# DWM1000Breakout.net
KiCad netlist of a schematic drawn in Altium Designer
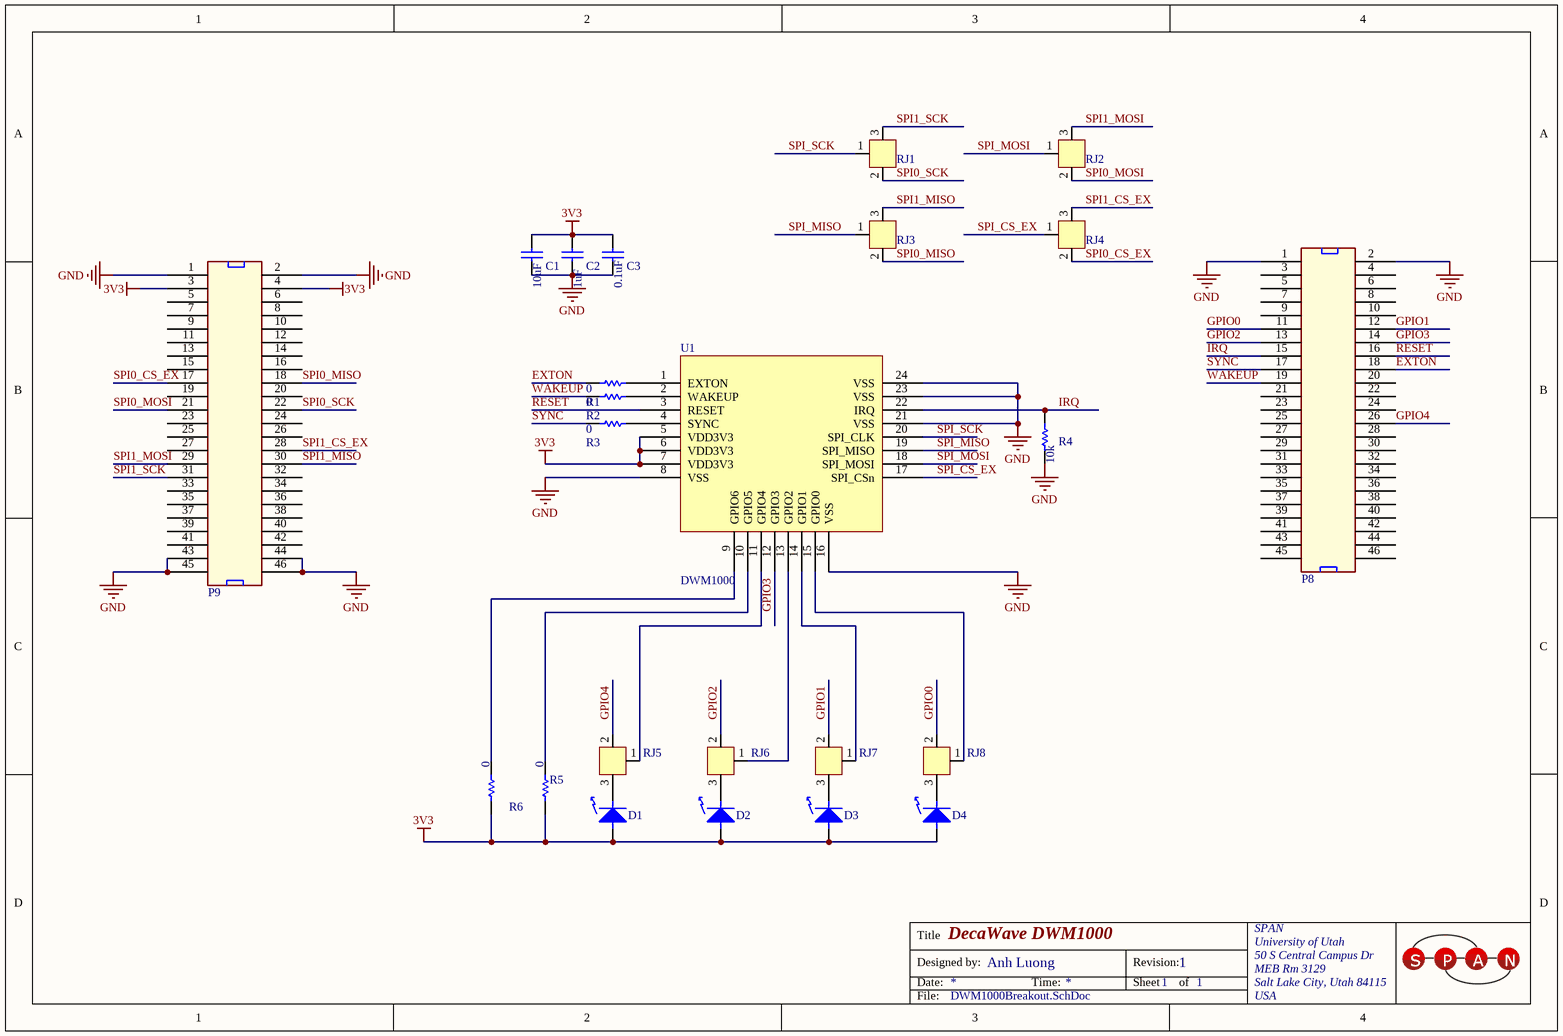
[diagram p0: DWM1000Breakout.SchDoc]

(export (version "E")
  (design (tool "Eeschema 10.0.6"))
  (components
    (comp (ref "C1")
      (value "GRM188R60J106ME47D")
      (footprint "CAPC1608X08N (0603)")
      (description "CAP CER 10UF 6.3V 20% X5R 0603")
      (fields
        (field (name "MANUFACTURER") "Murata Electronics North America")
        (field (name "TOLERANCE") "±20%")
      )
      (libsource (lib "DWM1000Breakout") (part "GRM188R60J106ME47D"))
    )
    (comp (ref "C2")
      (value "GRM188R61A105KA61D")
      (footprint "CAPC1608X08N (0603)")
      (description "CAP CER 1UF 10V 10% X5R 0603")
      (fields
        (field (name "MANUFACTURER") "Murata Electronics North America")
        (field (name "TOLERANCE") "±10%")
      )
      (libsource (lib "DWM1000Breakout") (part "GRM188R61A105KA61D"))
    )
    (comp (ref "C3")
      (value "GRM188R71C104KA01D")
      (footprint "CAPC1608X08N (0603)")
      (description "CAP CER 0.1UF 16V 10% X7R 0603")
      (fields
        (field (name "MANUFACTURER") "Murata Electronics North America")
        (field (name "TOLERANCE") "±10%")
      )
      (libsource (lib "DWM1000Breakout") (part "GRM188R71C104KA01D"))
    )
    (comp (ref "D1")
      (value "LG Q971-KN-1")
      (footprint "CHIPLED0603")
      (description "LED CHIPLED 570NM GREEN 0603 SMD")
      (fields (field (name "MANUFACTURER") "OSRAM Opto Semiconductors Inc"))
      (libsource (lib "DWM1000Breakout") (part "LG Q971-KN-1"))
    )
    (comp (ref "D2")
      (value "LG Q971-KN-1")
      (footprint "CHIPLED0603")
      (description "LED CHIPLED 570NM GREEN 0603 SMD")
      (fields (field (name "MANUFACTURER") "OSRAM Opto Semiconductors Inc"))
      (libsource (lib "DWM1000Breakout") (part "LG Q971-KN-1"))
    )
    (comp (ref "D3")
      (value "LG Q971-KN-1")
      (footprint "CHIPLED0603")
      (description "LED CHIPLED 570NM GREEN 0603 SMD")
      (fields (field (name "MANUFACTURER") "OSRAM Opto Semiconductors Inc"))
      (libsource (lib "DWM1000Breakout") (part "LG Q971-KN-1"))
    )
    (comp (ref "D4")
      (value "LG Q971-KN-1")
      (footprint "CHIPLED0603")
      (description "LED CHIPLED 570NM GREEN 0603 SMD")
      (fields (field (name "MANUFACTURER") "OSRAM Opto Semiconductors Inc"))
      (libsource (lib "DWM1000Breakout") (part "LG Q971-KN-1"))
    )
    (comp (ref "P8")
      (value "PREC023DAAN-RC")
      (footprint "HEADER23X2")
      (description "CONN HEADER .100\" DUAL STR 46POS")
      (fields (field (name "MANUFACTURER") "Sullins Connector Solutions"))
      (libsource (lib "Chronos") (part "PREC023DAAN-RC"))
    )
    (comp (ref "P9")
      (value "PREC023DAAN-RC")
      (footprint "HEADER23X2")
      (description "CONN HEADER .100\" DUAL STR 46POS")
      (fields (field (name "MANUFACTURER") "Sullins Connector Solutions"))
      (libsource (lib "Chronos") (part "PREC023DAAN-RC"))
    )
    (comp (ref "R1")
      (value "MCR03ERTJ000")
      (footprint "RESC1608X06N (0603)")
      (description "RES 0.0 OHM 1/10W JUMP 0603 SMD")
      (fields (field (name "MANUFACTURER") "Rohm Semiconductor") (field (name "TOLERANCE") "Jumper"))
      (libsource (lib "DWM1000Breakout") (part "MCR03ERTJ000"))
    )
    (comp (ref "R2")
      (value "MCR03ERTJ000")
      (footprint "RESC1608X06N (0603)")
      (description "RES 0.0 OHM 1/10W JUMP 0603 SMD")
      (fields (field (name "MANUFACTURER") "Rohm Semiconductor") (field (name "TOLERANCE") "Jumper"))
      (libsource (lib "DWM1000Breakout") (part "MCR03ERTJ000"))
    )
    (comp (ref "R3")
      (value "MCR03ERTJ000")
      (footprint "RESC1608X06N (0603)")
      (description "RES 0.0 OHM 1/10W JUMP 0603 SMD")
      (fields (field (name "MANUFACTURER") "Rohm Semiconductor") (field (name "TOLERANCE") "Jumper"))
      (libsource (lib "DWM1000Breakout") (part "MCR03ERTJ000"))
    )
    (comp (ref "R4")
      (value "MCR03ERTJ103")
      (footprint "RESC1608X06N (0603)")
      (description "RES 10K OHM 1/10W 5% 0603 SMD")
      (fields (field (name "MANUFACTURER") "Rohm Semiconductor") (field (name "TOLERANCE") "±5%"))
      (libsource (lib "DWM1000Breakout") (part "MCR03ERTJ103"))
    )
    (comp (ref "R5")
      (value "MCR03ERTJ000")
      (footprint "RESC1608X06N (0603)")
      (description "RES 0.0 OHM 1/10W JUMP 0603 SMD")
      (fields (field (name "MANUFACTURER") "Rohm Semiconductor") (field (name "TOLERANCE") "Jumper"))
      (libsource (lib "DWM1000Breakout") (part "MCR03ERTJ000"))
    )
    (comp (ref "R6")
      (value "MCR03ERTJ000")
      (footprint "RESC1608X06N (0603)")
      (description "RES 0.0 OHM 1/10W JUMP 0603 SMD")
      (fields (field (name "MANUFACTURER") "Rohm Semiconductor") (field (name "TOLERANCE") "Jumper"))
      (libsource (lib "DWM1000Breakout") (part "MCR03ERTJ000"))
    )
    (comp (ref "RJ1")
      (value "R_J")
      (footprint "RJ")
      (description "Resistor Jumper")
      (libsource (lib "DWM1000Breakout") (part "R_J"))
    )
    (comp (ref "RJ2")
      (value "R_J")
      (footprint "RJ")
      (description "Resistor Jumper")
      (libsource (lib "DWM1000Breakout") (part "R_J"))
    )
    (comp (ref "RJ3")
      (value "R_J")
      (footprint "RJ")
      (description "Resistor Jumper")
      (libsource (lib "DWM1000Breakout") (part "R_J"))
    )
    (comp (ref "RJ4")
      (value "R_J")
      (footprint "RJ")
      (description "Resistor Jumper")
      (libsource (lib "DWM1000Breakout") (part "R_J"))
    )
    (comp (ref "RJ5")
      (value "R_J")
      (footprint "RJ")
      (description "Resistor Jumper")
      (libsource (lib "") (part "R_J_1"))
    )
    (comp (ref "RJ6")
      (value "R_J")
      (footprint "RJ")
      (description "Resistor Jumper")
      (libsource (lib "") (part "R_J_1"))
    )
    (comp (ref "RJ7")
      (value "R_J")
      (footprint "RJ")
      (description "Resistor Jumper")
      (libsource (lib "") (part "R_J_1"))
    )
    (comp (ref "RJ8")
      (value "R_J")
      (footprint "RJ")
      (description "Resistor Jumper")
      (libsource (lib "") (part "R_J_1"))
    )
    (comp (ref "U1")
      (value "DWM1000")
      (footprint "DWM1000")
      (description "MOD IEEE802.15.4-2011 UWB TXRX")
      (fields (field (name "MANUFACTURER") "Decawave Limited"))
      (libsource (lib "DWM1000Breakout") (part "DWM1000"))
    )
  )
  (nets
    (net (code "1") (name "/EXTON") (class "Default")
      (node (ref "P8") (pin "18") (pinfunction "34_18") (pintype "passive"))
      (node (ref "R1") (pin "1") (pinfunction "1_1") (pintype "passive"))
    )
    (net (code "2") (name "/GPIO0") (class "Default")
      (node (ref "P8") (pin "11") (pinfunction "6_11") (pintype "passive"))
      (node (ref "RJ8") (pin "2") (pinfunction "2_2") (pintype "passive"))
    )
    (net (code "3") (name "/GPIO1") (class "Default")
      (node (ref "P8") (pin "12") (pinfunction "31_12") (pintype "passive"))
      (node (ref "RJ7") (pin "2") (pinfunction "2_2") (pintype "passive"))
    )
    (net (code "4") (name "/GPIO2") (class "Default")
      (node (ref "P8") (pin "13") (pinfunction "7_13") (pintype "passive"))
      (node (ref "RJ6") (pin "2") (pinfunction "2_2") (pintype "passive"))
    )
    (net (code "5") (name "/GPIO3") (class "Default")
      (node (ref "P8") (pin "14") (pinfunction "32_14") (pintype "passive"))
      (node (ref "U1") (pin "12") (pinfunction "GPIO3_12") (pintype "passive"))
    )
    (net (code "6") (name "/GPIO4") (class "Default")
      (node (ref "P8") (pin "26") (pinfunction "38_26") (pintype "passive"))
      (node (ref "RJ5") (pin "2") (pinfunction "2_2") (pintype "passive"))
    )
    (net (code "7") (name "/IRQ") (class "Default")
      (node (ref "P8") (pin "15") (pinfunction "8_15") (pintype "passive"))
      (node (ref "R4") (pin "2") (pinfunction "2_2") (pintype "passive"))
      (node (ref "U1") (pin "22") (pinfunction "IRQ_22") (pintype "passive"))
    )
    (net (code "8") (name "/RESET") (class "Default")
      (node (ref "P8") (pin "16") (pinfunction "33_16") (pintype "passive"))
      (node (ref "U1") (pin "3") (pinfunction "RESET_3") (pintype "passive"))
    )
    (net (code "9") (name "/SPI0_CS_EX") (class "Default")
      (node (ref "P9") (pin "17") (pinfunction "9_17") (pintype "passive"))
      (node (ref "RJ4") (pin "2") (pinfunction "2_2") (pintype "passive"))
    )
    (net (code "10") (name "/SPI0_MISO") (class "Default")
      (node (ref "P9") (pin "18") (pinfunction "34_18") (pintype "passive"))
      (node (ref "RJ3") (pin "2") (pinfunction "2_2") (pintype "passive"))
    )
    (net (code "11") (name "/SPI0_MOSI") (class "Default")
      (node (ref "P9") (pin "21") (pinfunction "11_21") (pintype "passive"))
      (node (ref "RJ2") (pin "2") (pinfunction "2_2") (pintype "passive"))
    )
    (net (code "12") (name "/SPI0_SCK") (class "Default")
      (node (ref "P9") (pin "22") (pinfunction "36_22") (pintype "passive"))
      (node (ref "RJ1") (pin "2") (pinfunction "2_2") (pintype "passive"))
    )
    (net (code "13") (name "/SPI1_CS_EX") (class "Default")
      (node (ref "P9") (pin "28") (pinfunction "39_28") (pintype "passive"))
      (node (ref "RJ4") (pin "3") (pinfunction "3_3") (pintype "passive"))
    )
    (net (code "14") (name "/SPI1_MISO") (class "Default")
      (node (ref "P9") (pin "30") (pinfunction "40_30") (pintype "passive"))
      (node (ref "RJ3") (pin "3") (pinfunction "3_3") (pintype "passive"))
    )
    (net (code "15") (name "/SPI1_MOSI") (class "Default")
      (node (ref "P9") (pin "29") (pinfunction "15_29") (pintype "passive"))
      (node (ref "RJ2") (pin "3") (pinfunction "3_3") (pintype "passive"))
    )
    (net (code "16") (name "/SPI1_SCK") (class "Default")
      (node (ref "P9") (pin "31") (pinfunction "16_31") (pintype "passive"))
      (node (ref "RJ1") (pin "3") (pinfunction "3_3") (pintype "passive"))
    )
    (net (code "17") (name "/SPI_CS_EX") (class "Default")
      (node (ref "RJ4") (pin "1") (pinfunction "1_1") (pintype "passive"))
      (node (ref "U1") (pin "17") (pinfunction "SPI_CSn_17") (pintype "passive"))
    )
    (net (code "18") (name "/SPI_MISO") (class "Default")
      (node (ref "RJ3") (pin "1") (pinfunction "1_1") (pintype "passive"))
      (node (ref "U1") (pin "19") (pinfunction "SPI_MISO_19") (pintype "passive"))
    )
    (net (code "19") (name "/SPI_MOSI") (class "Default")
      (node (ref "RJ2") (pin "1") (pinfunction "1_1") (pintype "passive"))
      (node (ref "U1") (pin "18") (pinfunction "SPI_MOSI_18") (pintype "passive"))
    )
    (net (code "20") (name "/SPI_SCK") (class "Default")
      (node (ref "RJ1") (pin "1") (pinfunction "1_1") (pintype "passive"))
      (node (ref "U1") (pin "20") (pinfunction "SPI_CLK_20") (pintype "passive"))
    )
    (net (code "21") (name "/SYNC") (class "Default")
      (node (ref "P8") (pin "17") (pinfunction "9_17") (pintype "passive"))
      (node (ref "R3") (pin "1") (pinfunction "1_1") (pintype "passive"))
    )
    (net (code "22") (name "/WAKEUP") (class "Default")
      (node (ref "P8") (pin "19") (pinfunction "10_19") (pintype "passive"))
      (node (ref "R2") (pin "1") (pinfunction "1_1") (pintype "passive"))
    )
    (net (code "23") (name "3V3") (class "Default")
      (node (ref "C1") (pin "2") (pinfunction "2_2") (pintype "passive"))
      (node (ref "C2") (pin "2") (pinfunction "2_2") (pintype "passive"))
      (node (ref "C3") (pin "2") (pinfunction "2_2") (pintype "passive"))
      (node (ref "D1") (pin "1") (pinfunction "1_1") (pintype "passive"))
      (node (ref "D2") (pin "1") (pinfunction "1_1") (pintype "passive"))
      (node (ref "D3") (pin "1") (pinfunction "1_1") (pintype "passive"))
      (node (ref "D4") (pin "1") (pinfunction "1_1") (pintype "passive"))
      (node (ref "P9") (pin "3") (pinfunction "2_3") (pintype "passive"))
      (node (ref "P9") (pin "4") (pinfunction "27_4") (pintype "passive"))
      (node (ref "R5") (pin "2") (pinfunction "2_2") (pintype "passive"))
      (node (ref "R6") (pin "2") (pinfunction "2_2") (pintype "passive"))
      (node (ref "U1") (pin "5") (pinfunction "VDD3V3_5") (pintype "passive"))
      (node (ref "U1") (pin "6") (pinfunction "VDD3V3_6") (pintype "passive"))
      (node (ref "U1") (pin "7") (pinfunction "VDD3V3_7") (pintype "passive"))
    )
    (net (code "24") (name "GND") (class "Default")
      (node (ref "C1") (pin "1") (pinfunction "1_1") (pintype "passive"))
      (node (ref "C2") (pin "1") (pinfunction "1_1") (pintype "passive"))
      (node (ref "C3") (pin "1") (pinfunction "1_1") (pintype "passive"))
      (node (ref "P8") (pin "1") (pinfunction "1_1") (pintype "passive"))
      (node (ref "P8") (pin "2") (pinfunction "26_2") (pintype "passive"))
      (node (ref "P9") (pin "1") (pinfunction "1_1") (pintype "passive"))
      (node (ref "P9") (pin "2") (pinfunction "26_2") (pintype "passive"))
      (node (ref "P9") (pin "43") (pinfunction "22_43") (pintype "passive"))
      (node (ref "P9") (pin "44") (pinfunction "47_44") (pintype "passive"))
      (node (ref "P9") (pin "45") (pinfunction "23_45") (pintype "passive"))
      (node (ref "P9") (pin "46") (pinfunction "48_46") (pintype "passive"))
      (node (ref "R4") (pin "1") (pinfunction "1_1") (pintype "passive"))
      (node (ref "U1") (pin "16") (pinfunction "VSS_16") (pintype "passive"))
      (node (ref "U1") (pin "21") (pinfunction "VSS_21") (pintype "passive"))
      (node (ref "U1") (pin "23") (pinfunction "VSS_23") (pintype "passive"))
      (node (ref "U1") (pin "24") (pinfunction "VSS_24") (pintype "passive"))
      (node (ref "U1") (pin "8") (pinfunction "VSS_8") (pintype "passive"))
    )
    (net (code "25") (name "Net-(D1-Pad2)") (class "Default")
      (node (ref "D1") (pin "2") (pinfunction "2_2") (pintype "passive"))
      (node (ref "RJ5") (pin "3") (pinfunction "3_3") (pintype "passive"))
    )
    (net (code "26") (name "Net-(D2-Pad2)") (class "Default")
      (node (ref "D2") (pin "2") (pinfunction "2_2") (pintype "passive"))
      (node (ref "RJ6") (pin "3") (pinfunction "3_3") (pintype "passive"))
    )
    (net (code "27") (name "Net-(D3-Pad2)") (class "Default")
      (node (ref "D3") (pin "2") (pinfunction "2_2") (pintype "passive"))
      (node (ref "RJ7") (pin "3") (pinfunction "3_3") (pintype "passive"))
    )
    (net (code "28") (name "Net-(D4-Pad2)") (class "Default")
      (node (ref "D4") (pin "2") (pinfunction "2_2") (pintype "passive"))
      (node (ref "RJ8") (pin "3") (pinfunction "3_3") (pintype "passive"))
    )
    (net (code "29") (name "Net-(U1-EXTON)") (class "Default")
      (node (ref "R1") (pin "2") (pinfunction "2_2") (pintype "passive"))
      (node (ref "U1") (pin "1") (pinfunction "EXTON_1") (pintype "passive"))
    )
    (net (code "30") (name "Net-(U1-GPIO0)") (class "Default")
      (node (ref "RJ8") (pin "1") (pinfunction "1_1") (pintype "passive"))
      (node (ref "U1") (pin "15") (pinfunction "GPIO0_15") (pintype "passive"))
    )
    (net (code "31") (name "Net-(U1-GPIO1)") (class "Default")
      (node (ref "RJ7") (pin "1") (pinfunction "1_1") (pintype "passive"))
      (node (ref "U1") (pin "14") (pinfunction "GPIO1_14") (pintype "passive"))
    )
    (net (code "32") (name "Net-(U1-GPIO2)") (class "Default")
      (node (ref "RJ6") (pin "1") (pinfunction "1_1") (pintype "passive"))
      (node (ref "U1") (pin "13") (pinfunction "GPIO2_13") (pintype "passive"))
    )
    (net (code "33") (name "Net-(U1-GPIO4)") (class "Default")
      (node (ref "RJ5") (pin "1") (pinfunction "1_1") (pintype "passive"))
      (node (ref "U1") (pin "11") (pinfunction "GPIO4_11") (pintype "passive"))
    )
    (net (code "34") (name "Net-(U1-GPIO5)") (class "Default")
      (node (ref "R5") (pin "1") (pinfunction "1_1") (pintype "passive"))
      (node (ref "U1") (pin "10") (pinfunction "GPIO5_10") (pintype "passive"))
    )
    (net (code "35") (name "Net-(U1-GPIO6)") (class "Default")
      (node (ref "R6") (pin "1") (pinfunction "1_1") (pintype "passive"))
      (node (ref "U1") (pin "9") (pinfunction "GPIO6_9") (pintype "passive"))
    )
    (net (code "36") (name "Net-(U1-SYNC)") (class "Default")
      (node (ref "R3") (pin "2") (pinfunction "2_2") (pintype "passive"))
      (node (ref "U1") (pin "4") (pinfunction "SYNC_4") (pintype "passive"))
    )
    (net (code "37") (name "Net-(U1-WAKEUP)") (class "Default")
      (node (ref "R2") (pin "2") (pinfunction "2_2") (pintype "passive"))
      (node (ref "U1") (pin "2") (pinfunction "WAKEUP_2") (pintype "passive"))
    )
    (net (code "38") (name "unconnected-(P8-2-Pad3)") (class "Default")
      (node (ref "P8") (pin "3") (pinfunction "2_3") (pintype "passive"))
    )
    (net (code "39") (name "unconnected-(P8-3-Pad5)") (class "Default")
      (node (ref "P8") (pin "5") (pinfunction "3_5") (pintype "passive"))
    )
    (net (code "40") (name "unconnected-(P8-4-Pad7)") (class "Default")
      (node (ref "P8") (pin "7") (pinfunction "4_7") (pintype "passive"))
    )
    (net (code "41") (name "unconnected-(P8-5-Pad9)") (class "Default")
      (node (ref "P8") (pin "9") (pinfunction "5_9") (pintype "passive"))
    )
    (net (code "42") (name "unconnected-(P8-11-Pad21)") (class "Default")
      (node (ref "P8") (pin "21") (pinfunction "11_21") (pintype "passive"))
    )
    (net (code "43") (name "unconnected-(P8-12-Pad23)") (class "Default")
      (node (ref "P8") (pin "23") (pinfunction "12_23") (pintype "passive"))
    )
    (net (code "44") (name "unconnected-(P8-13-Pad25)") (class "Default")
      (node (ref "P8") (pin "25") (pinfunction "13_25") (pintype "passive"))
    )
    (net (code "45") (name "unconnected-(P8-14-Pad27)") (class "Default")
      (node (ref "P8") (pin "27") (pinfunction "14_27") (pintype "passive"))
    )
    (net (code "46") (name "unconnected-(P8-15-Pad29)") (class "Default")
      (node (ref "P8") (pin "29") (pinfunction "15_29") (pintype "passive"))
    )
    (net (code "47") (name "unconnected-(P8-16-Pad31)") (class "Default")
      (node (ref "P8") (pin "31") (pinfunction "16_31") (pintype "passive"))
    )
    (net (code "48") (name "unconnected-(P8-17-Pad33)") (class "Default")
      (node (ref "P8") (pin "33") (pinfunction "17_33") (pintype "passive"))
    )
    (net (code "49") (name "unconnected-(P8-18-Pad35)") (class "Default")
      (node (ref "P8") (pin "35") (pinfunction "18_35") (pintype "passive"))
    )
    (net (code "50") (name "unconnected-(P8-19-Pad37)") (class "Default")
      (node (ref "P8") (pin "37") (pinfunction "19_37") (pintype "passive"))
    )
    (net (code "51") (name "unconnected-(P8-20-Pad39)") (class "Default")
      (node (ref "P8") (pin "39") (pinfunction "20_39") (pintype "passive"))
    )
    (net (code "52") (name "unconnected-(P8-21-Pad41)") (class "Default")
      (node (ref "P8") (pin "41") (pinfunction "21_41") (pintype "passive"))
    )
    (net (code "53") (name "unconnected-(P8-22-Pad43)") (class "Default")
      (node (ref "P8") (pin "43") (pinfunction "22_43") (pintype "passive"))
    )
    (net (code "54") (name "unconnected-(P8-23-Pad45)") (class "Default")
      (node (ref "P8") (pin "45") (pinfunction "23_45") (pintype "passive"))
    )
    (net (code "55") (name "unconnected-(P8-27-Pad4)") (class "Default")
      (node (ref "P8") (pin "4") (pinfunction "27_4") (pintype "passive"))
    )
    (net (code "56") (name "unconnected-(P8-28-Pad6)") (class "Default")
      (node (ref "P8") (pin "6") (pinfunction "28_6") (pintype "passive"))
    )
    (net (code "57") (name "unconnected-(P8-29-Pad8)") (class "Default")
      (node (ref "P8") (pin "8") (pinfunction "29_8") (pintype "passive"))
    )
    (net (code "58") (name "unconnected-(P8-30-Pad10)") (class "Default")
      (node (ref "P8") (pin "10") (pinfunction "30_10") (pintype "passive"))
    )
    (net (code "59") (name "unconnected-(P8-35-Pad20)") (class "Default")
      (node (ref "P8") (pin "20") (pinfunction "35_20") (pintype "passive"))
    )
    (net (code "60") (name "unconnected-(P8-36-Pad22)") (class "Default")
      (node (ref "P8") (pin "22") (pinfunction "36_22") (pintype "passive"))
    )
    (net (code "61") (name "unconnected-(P8-37-Pad24)") (class "Default")
      (node (ref "P8") (pin "24") (pinfunction "37_24") (pintype "passive"))
    )
    (net (code "62") (name "unconnected-(P8-39-Pad28)") (class "Default")
      (node (ref "P8") (pin "28") (pinfunction "39_28") (pintype "passive"))
    )
    (net (code "63") (name "unconnected-(P8-40-Pad30)") (class "Default")
      (node (ref "P8") (pin "30") (pinfunction "40_30") (pintype "passive"))
    )
    (net (code "64") (name "unconnected-(P8-41-Pad32)") (class "Default")
      (node (ref "P8") (pin "32") (pinfunction "41_32") (pintype "passive"))
    )
    (net (code "65") (name "unconnected-(P8-42-Pad34)") (class "Default")
      (node (ref "P8") (pin "34") (pinfunction "42_34") (pintype "passive"))
    )
    (net (code "66") (name "unconnected-(P8-43-Pad36)") (class "Default")
      (node (ref "P8") (pin "36") (pinfunction "43_36") (pintype "passive"))
    )
    (net (code "67") (name "unconnected-(P8-44-Pad38)") (class "Default")
      (node (ref "P8") (pin "38") (pinfunction "44_38") (pintype "passive"))
    )
    (net (code "68") (name "unconnected-(P8-45-Pad40)") (class "Default")
      (node (ref "P8") (pin "40") (pinfunction "45_40") (pintype "passive"))
    )
    (net (code "69") (name "unconnected-(P8-46-Pad42)") (class "Default")
      (node (ref "P8") (pin "42") (pinfunction "46_42") (pintype "passive"))
    )
    (net (code "70") (name "unconnected-(P8-47-Pad44)") (class "Default")
      (node (ref "P8") (pin "44") (pinfunction "47_44") (pintype "passive"))
    )
    (net (code "71") (name "unconnected-(P8-48-Pad46)") (class "Default")
      (node (ref "P8") (pin "46") (pinfunction "48_46") (pintype "passive"))
    )
    (net (code "72") (name "unconnected-(P9-3-Pad5)") (class "Default")
      (node (ref "P9") (pin "5") (pinfunction "3_5") (pintype "passive"))
    )
    (net (code "73") (name "unconnected-(P9-4-Pad7)") (class "Default")
      (node (ref "P9") (pin "7") (pinfunction "4_7") (pintype "passive"))
    )
    (net (code "74") (name "unconnected-(P9-5-Pad9)") (class "Default")
      (node (ref "P9") (pin "9") (pinfunction "5_9") (pintype "passive"))
    )
    (net (code "75") (name "unconnected-(P9-6-Pad11)") (class "Default")
      (node (ref "P9") (pin "11") (pinfunction "6_11") (pintype "passive"))
    )
    (net (code "76") (name "unconnected-(P9-7-Pad13)") (class "Default")
      (node (ref "P9") (pin "13") (pinfunction "7_13") (pintype "passive"))
    )
    (net (code "77") (name "unconnected-(P9-8-Pad15)") (class "Default")
      (node (ref "P9") (pin "15") (pinfunction "8_15") (pintype "passive"))
    )
    (net (code "78") (name "unconnected-(P9-10-Pad19)") (class "Default")
      (node (ref "P9") (pin "19") (pinfunction "10_19") (pintype "passive"))
    )
    (net (code "79") (name "unconnected-(P9-12-Pad23)") (class "Default")
      (node (ref "P9") (pin "23") (pinfunction "12_23") (pintype "passive"))
    )
    (net (code "80") (name "unconnected-(P9-13-Pad25)") (class "Default")
      (node (ref "P9") (pin "25") (pinfunction "13_25") (pintype "passive"))
    )
    (net (code "81") (name "unconnected-(P9-14-Pad27)") (class "Default")
      (node (ref "P9") (pin "27") (pinfunction "14_27") (pintype "passive"))
    )
    (net (code "82") (name "unconnected-(P9-17-Pad33)") (class "Default")
      (node (ref "P9") (pin "33") (pinfunction "17_33") (pintype "passive"))
    )
    (net (code "83") (name "unconnected-(P9-18-Pad35)") (class "Default")
      (node (ref "P9") (pin "35") (pinfunction "18_35") (pintype "passive"))
    )
    (net (code "84") (name "unconnected-(P9-19-Pad37)") (class "Default")
      (node (ref "P9") (pin "37") (pinfunction "19_37") (pintype "passive"))
    )
    (net (code "85") (name "unconnected-(P9-20-Pad39)") (class "Default")
      (node (ref "P9") (pin "39") (pinfunction "20_39") (pintype "passive"))
    )
    (net (code "86") (name "unconnected-(P9-21-Pad41)") (class "Default")
      (node (ref "P9") (pin "41") (pinfunction "21_41") (pintype "passive"))
    )
    (net (code "87") (name "unconnected-(P9-28-Pad6)") (class "Default")
      (node (ref "P9") (pin "6") (pinfunction "28_6") (pintype "passive"))
    )
    (net (code "88") (name "unconnected-(P9-29-Pad8)") (class "Default")
      (node (ref "P9") (pin "8") (pinfunction "29_8") (pintype "passive"))
    )
    (net (code "89") (name "unconnected-(P9-30-Pad10)") (class "Default")
      (node (ref "P9") (pin "10") (pinfunction "30_10") (pintype "passive"))
    )
    (net (code "90") (name "unconnected-(P9-31-Pad12)") (class "Default")
      (node (ref "P9") (pin "12") (pinfunction "31_12") (pintype "passive"))
    )
    (net (code "91") (name "unconnected-(P9-32-Pad14)") (class "Default")
      (node (ref "P9") (pin "14") (pinfunction "32_14") (pintype "passive"))
    )
    (net (code "92") (name "unconnected-(P9-33-Pad16)") (class "Default")
      (node (ref "P9") (pin "16") (pinfunction "33_16") (pintype "passive"))
    )
    (net (code "93") (name "unconnected-(P9-35-Pad20)") (class "Default")
      (node (ref "P9") (pin "20") (pinfunction "35_20") (pintype "passive"))
    )
    (net (code "94") (name "unconnected-(P9-37-Pad24)") (class "Default")
      (node (ref "P9") (pin "24") (pinfunction "37_24") (pintype "passive"))
    )
    (net (code "95") (name "unconnected-(P9-38-Pad26)") (class "Default")
      (node (ref "P9") (pin "26") (pinfunction "38_26") (pintype "passive"))
    )
    (net (code "96") (name "unconnected-(P9-41-Pad32)") (class "Default")
      (node (ref "P9") (pin "32") (pinfunction "41_32") (pintype "passive"))
    )
    (net (code "97") (name "unconnected-(P9-42-Pad34)") (class "Default")
      (node (ref "P9") (pin "34") (pinfunction "42_34") (pintype "passive"))
    )
    (net (code "98") (name "unconnected-(P9-43-Pad36)") (class "Default")
      (node (ref "P9") (pin "36") (pinfunction "43_36") (pintype "passive"))
    )
    (net (code "99") (name "unconnected-(P9-44-Pad38)") (class "Default")
      (node (ref "P9") (pin "38") (pinfunction "44_38") (pintype "passive"))
    )
    (net (code "100") (name "unconnected-(P9-45-Pad40)") (class "Default")
      (node (ref "P9") (pin "40") (pinfunction "45_40") (pintype "passive"))
    )
    (net (code "101") (name "unconnected-(P9-46-Pad42)") (class "Default")
      (node (ref "P9") (pin "42") (pinfunction "46_42") (pintype "passive"))
    )
  )
)
